# H_Bridge_Motor_Driver_Circuit.net
KiCad netlist of a schematic drawn in EAGLE
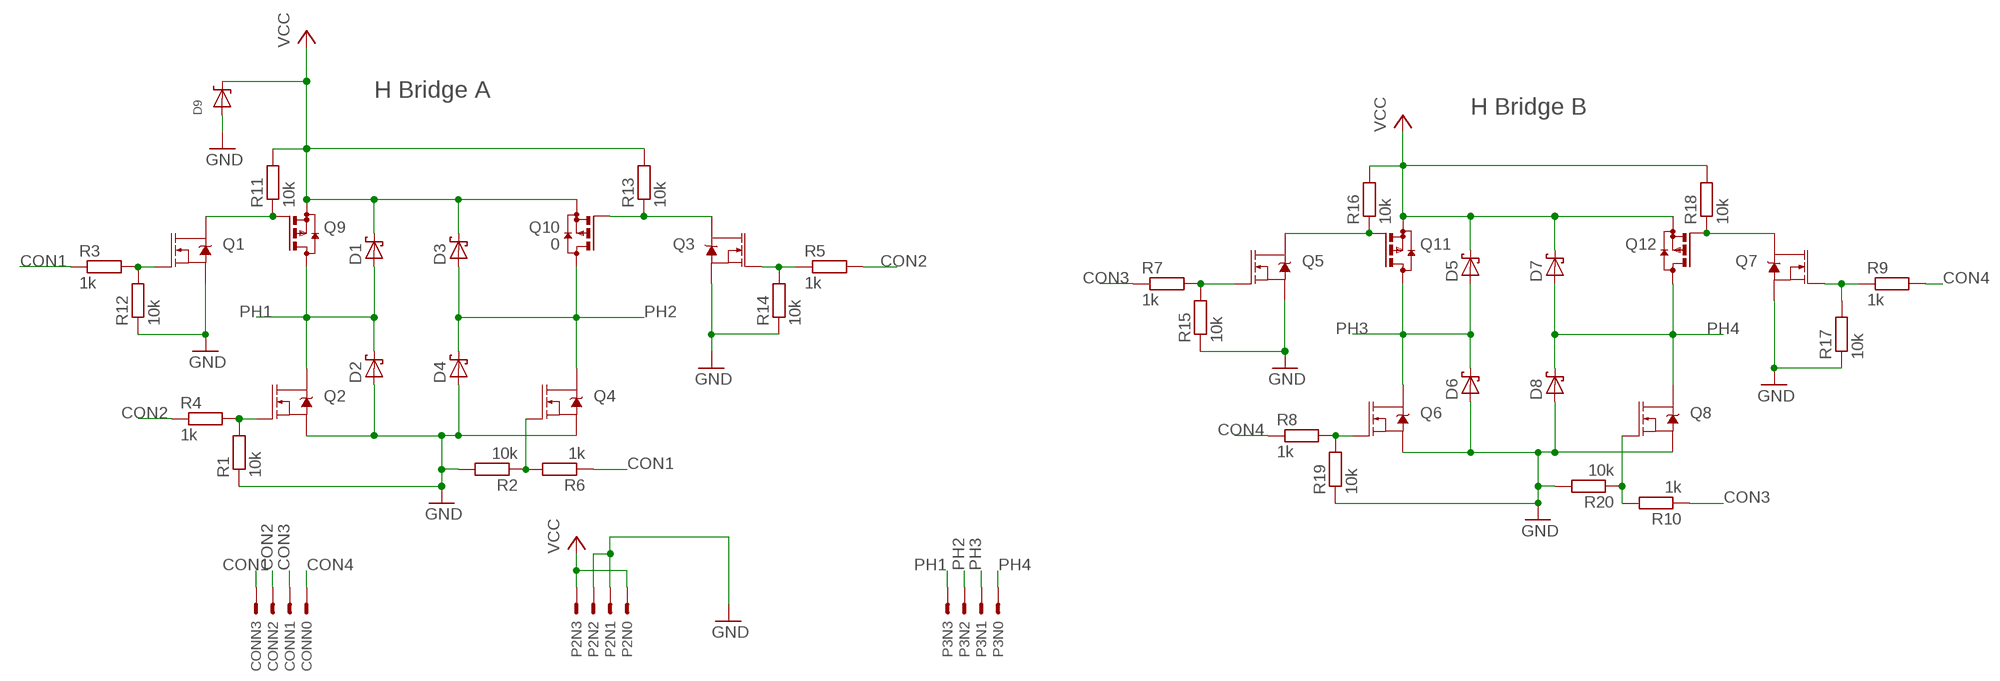
[diagram p0: schematic, sheet 1]

(export (version "E")
  (design (tool "Eeschema 10.0.6"))
  (components
    (comp (ref "CON")
      (value "4PINHEADER")
      (footprint "eagle-import:4PINHEADER")
      (libsource (lib "eagle-import") (part "4PINHEADER"))
    )
    (comp (ref "D1")
      (value "BAS40")
      (footprint "eagle-import:SOT23")
      (libsource (lib "eagle-import") (part "BAS40"))
    )
    (comp (ref "D2")
      (value "BAS40")
      (footprint "eagle-import:SOT23")
      (libsource (lib "eagle-import") (part "BAS40"))
    )
    (comp (ref "D3")
      (value "BAS40")
      (footprint "eagle-import:SOT23")
      (libsource (lib "eagle-import") (part "BAS40"))
    )
    (comp (ref "D4")
      (value "BAS40")
      (footprint "eagle-import:SOT23")
      (libsource (lib "eagle-import") (part "BAS40"))
    )
    (comp (ref "D5")
      (value "BAS40")
      (footprint "eagle-import:SOT23")
      (libsource (lib "eagle-import") (part "BAS40"))
    )
    (comp (ref "D6")
      (value "BAS40")
      (footprint "eagle-import:SOT23")
      (libsource (lib "eagle-import") (part "BAS40"))
    )
    (comp (ref "D7")
      (value "BAS40")
      (footprint "eagle-import:SOT23")
      (libsource (lib "eagle-import") (part "BAS40"))
    )
    (comp (ref "D8")
      (value "BAS40")
      (footprint "eagle-import:SOT23")
      (libsource (lib "eagle-import") (part "BAS40"))
    )
    (comp (ref "D9")
      (value "DDZ5V6ASF")
      (footprint "eagle-import:DDZ5V6ASF")
      (libsource (lib "eagle-import") (part "DDZ5V6ASF"))
    )
    (comp (ref "P2")
      (value "4PINHEADER")
      (footprint "eagle-import:4PINHEADER")
      (libsource (lib "eagle-import") (part "4PINHEADER"))
    )
    (comp (ref "P3")
      (value "4PINHEADER")
      (footprint "eagle-import:4PINHEADER")
      (libsource (lib "eagle-import") (part "4PINHEADER"))
    )
    (comp (ref "Q1")
      (value "MOSFET-NCH-BSS138")
      (footprint "eagle-import:SOT23-3")
      (libsource (lib "eagle-import") (part "MOSFET-NCH-BSS138"))
    )
    (comp (ref "Q2")
      (value "MOSFET-NCH-BSS138")
      (footprint "eagle-import:SOT23-3")
      (libsource (lib "eagle-import") (part "MOSFET-NCH-BSS138"))
    )
    (comp (ref "Q3")
      (value "MOSFET-NCH-BSS138")
      (footprint "eagle-import:SOT23-3")
      (libsource (lib "eagle-import") (part "MOSFET-NCH-BSS138"))
    )
    (comp (ref "Q4")
      (value "MOSFET-NCH-BSS138")
      (footprint "eagle-import:SOT23-3")
      (libsource (lib "eagle-import") (part "MOSFET-NCH-BSS138"))
    )
    (comp (ref "Q5")
      (value "MOSFET-NCH-BSS138")
      (footprint "eagle-import:SOT23-3")
      (libsource (lib "eagle-import") (part "MOSFET-NCH-BSS138"))
    )
    (comp (ref "Q6")
      (value "MOSFET-NCH-BSS138")
      (footprint "eagle-import:SOT23-3")
      (libsource (lib "eagle-import") (part "MOSFET-NCH-BSS138"))
    )
    (comp (ref "Q7")
      (value "MOSFET-NCH-BSS138")
      (footprint "eagle-import:SOT23-3")
      (libsource (lib "eagle-import") (part "MOSFET-NCH-BSS138"))
    )
    (comp (ref "Q8")
      (value "MOSFET-NCH-BSS138")
      (footprint "eagle-import:SOT23-3")
      (libsource (lib "eagle-import") (part "MOSFET-NCH-BSS138"))
    )
    (comp (ref "Q9")
      (value "BSS84")
      (footprint "eagle-import:SOT23")
      (libsource (lib "eagle-import") (part "BSS84"))
    )
    (comp (ref "Q10")
      (value "0")
      (footprint "eagle-import:SOT23")
      (libsource (lib "eagle-import") (part "BSS84"))
    )
    (comp (ref "Q11")
      (value "BSS84")
      (footprint "eagle-import:SOT23")
      (libsource (lib "eagle-import") (part "BSS84"))
    )
    (comp (ref "Q12")
      (value "BSS84")
      (footprint "eagle-import:SOT23")
      (libsource (lib "eagle-import") (part "BSS84"))
    )
    (comp (ref "R1")
      (value "10k")
      (footprint "eagle-import:R1206")
      (libsource (lib "eagle-import") (part "R-EU_R1206"))
    )
    (comp (ref "R2")
      (value "10k")
      (footprint "eagle-import:R1206")
      (libsource (lib "eagle-import") (part "R-EU_R1206"))
    )
    (comp (ref "R3")
      (value "1k")
      (footprint "eagle-import:R1206")
      (libsource (lib "eagle-import") (part "R-EU_R1206"))
    )
    (comp (ref "R4")
      (value "1k")
      (footprint "eagle-import:R1206")
      (libsource (lib "eagle-import") (part "R-EU_R1206"))
    )
    (comp (ref "R5")
      (value "1k")
      (footprint "eagle-import:R1206")
      (libsource (lib "eagle-import") (part "R-EU_R1206"))
    )
    (comp (ref "R6")
      (value "1k")
      (footprint "eagle-import:R1206")
      (libsource (lib "eagle-import") (part "R-EU_R1206"))
    )
    (comp (ref "R7")
      (value "1k")
      (footprint "eagle-import:R1206")
      (libsource (lib "eagle-import") (part "R-EU_R1206"))
    )
    (comp (ref "R8")
      (value "1k")
      (footprint "eagle-import:R1206")
      (libsource (lib "eagle-import") (part "R-EU_R1206"))
    )
    (comp (ref "R9")
      (value "1k")
      (footprint "eagle-import:R1206")
      (libsource (lib "eagle-import") (part "R-EU_R1206"))
    )
    (comp (ref "R10")
      (value "1k")
      (footprint "eagle-import:R1206")
      (libsource (lib "eagle-import") (part "R-EU_R1206"))
    )
    (comp (ref "R11")
      (value "10k")
      (footprint "eagle-import:R1206")
      (libsource (lib "eagle-import") (part "R-EU_R1206"))
    )
    (comp (ref "R12")
      (value "10k")
      (footprint "eagle-import:R1206")
      (libsource (lib "eagle-import") (part "R-EU_R1206"))
    )
    (comp (ref "R13")
      (value "10k")
      (footprint "eagle-import:R1206")
      (libsource (lib "eagle-import") (part "R-EU_R1206"))
    )
    (comp (ref "R14")
      (value "10k")
      (footprint "eagle-import:R1206")
      (libsource (lib "eagle-import") (part "R-EU_R1206"))
    )
    (comp (ref "R15")
      (value "10k")
      (footprint "eagle-import:R1206")
      (libsource (lib "eagle-import") (part "R-EU_R1206"))
    )
    (comp (ref "R16")
      (value "10k")
      (footprint "eagle-import:R1206")
      (libsource (lib "eagle-import") (part "R-EU_R1206"))
    )
    (comp (ref "R17")
      (value "10k")
      (footprint "eagle-import:R1206")
      (libsource (lib "eagle-import") (part "R-EU_R1206"))
    )
    (comp (ref "R18")
      (value "10k")
      (footprint "eagle-import:R1206")
      (libsource (lib "eagle-import") (part "R-EU_R1206"))
    )
    (comp (ref "R19")
      (value "10k")
      (footprint "eagle-import:R1206")
      (libsource (lib "eagle-import") (part "R-EU_R1206"))
    )
    (comp (ref "R20")
      (value "10k")
      (footprint "eagle-import:R1206")
      (libsource (lib "eagle-import") (part "R-EU_R1206"))
    )
  )
  (nets
    (net (code "1") (name "/CON1") (class "Default")
      (node (ref "CON") (pin "N3") (pinfunction "S_N3") (pintype "passive"))
      (node (ref "R3") (pin "1") (pinfunction "1_1") (pintype "passive"))
      (node (ref "R6") (pin "1") (pinfunction "1_1") (pintype "passive"))
    )
    (net (code "2") (name "/CON2") (class "Default")
      (node (ref "CON") (pin "N2") (pinfunction "S_N2") (pintype "passive"))
      (node (ref "R4") (pin "1") (pinfunction "1_1") (pintype "passive"))
      (node (ref "R5") (pin "2") (pinfunction "2_2") (pintype "passive"))
    )
    (net (code "3") (name "/CON3") (class "Default")
      (node (ref "CON") (pin "N1") (pinfunction "S_N1") (pintype "passive"))
      (node (ref "R10") (pin "1") (pinfunction "1_1") (pintype "passive"))
      (node (ref "R7") (pin "1") (pinfunction "1_1") (pintype "passive"))
    )
    (net (code "4") (name "/CON4") (class "Default")
      (node (ref "CON") (pin "N0") (pinfunction "S_N0") (pintype "passive"))
      (node (ref "R8") (pin "1") (pinfunction "1_1") (pintype "passive"))
      (node (ref "R9") (pin "2") (pinfunction "2_2") (pintype "passive"))
    )
    (net (code "5") (name "/PH1") (class "Default")
      (node (ref "D1") (pin "1") (pinfunction "A_1") (pintype "passive"))
      (node (ref "D2") (pin "3") (pinfunction "C_3") (pintype "passive"))
      (node (ref "P3") (pin "N3") (pinfunction "S_N3") (pintype "passive"))
      (node (ref "Q2") (pin "3") (pinfunction "D_3") (pintype "bidirectional"))
      (node (ref "Q9") (pin "3") (pinfunction "D_3") (pintype "passive"))
    )
    (net (code "6") (name "/PH2") (class "Default")
      (node (ref "D3") (pin "1") (pinfunction "A_1") (pintype "passive"))
      (node (ref "D4") (pin "3") (pinfunction "C_3") (pintype "passive"))
      (node (ref "P3") (pin "N2") (pinfunction "S_N2") (pintype "passive"))
      (node (ref "Q10") (pin "3") (pinfunction "D_3") (pintype "passive"))
      (node (ref "Q4") (pin "3") (pinfunction "D_3") (pintype "bidirectional"))
    )
    (net (code "7") (name "/PH3") (class "Default")
      (node (ref "D5") (pin "1") (pinfunction "A_1") (pintype "passive"))
      (node (ref "D6") (pin "3") (pinfunction "C_3") (pintype "passive"))
      (node (ref "P3") (pin "N1") (pinfunction "S_N1") (pintype "passive"))
      (node (ref "Q11") (pin "3") (pinfunction "D_3") (pintype "passive"))
      (node (ref "Q6") (pin "3") (pinfunction "D_3") (pintype "bidirectional"))
    )
    (net (code "8") (name "/PH4") (class "Default")
      (node (ref "D7") (pin "1") (pinfunction "A_1") (pintype "passive"))
      (node (ref "D8") (pin "3") (pinfunction "C_3") (pintype "passive"))
      (node (ref "P3") (pin "N0") (pinfunction "S_N0") (pintype "passive"))
      (node (ref "Q12") (pin "3") (pinfunction "D_3") (pintype "passive"))
      (node (ref "Q8") (pin "3") (pinfunction "D_3") (pintype "bidirectional"))
    )
    (net (code "9") (name "GND") (class "Default")
      (node (ref "D2") (pin "1") (pinfunction "A_1") (pintype "passive"))
      (node (ref "D4") (pin "1") (pinfunction "A_1") (pintype "passive"))
      (node (ref "D6") (pin "1") (pinfunction "A_1") (pintype "passive"))
      (node (ref "D8") (pin "1") (pinfunction "A_1") (pintype "passive"))
      (node (ref "D9") (pin "P$1") (pinfunction "A_P$1") (pintype "passive"))
      (node (ref "P2") (pin "N1") (pinfunction "S_N1") (pintype "passive"))
      (node (ref "P2") (pin "N2") (pinfunction "S_N2") (pintype "passive"))
      (node (ref "Q1") (pin "2") (pinfunction "S_2") (pintype "bidirectional"))
      (node (ref "Q2") (pin "2") (pinfunction "S_2") (pintype "bidirectional"))
      (node (ref "Q3") (pin "2") (pinfunction "S_2") (pintype "bidirectional"))
      (node (ref "Q4") (pin "2") (pinfunction "S_2") (pintype "bidirectional"))
      (node (ref "Q5") (pin "2") (pinfunction "S_2") (pintype "bidirectional"))
      (node (ref "Q6") (pin "2") (pinfunction "S_2") (pintype "bidirectional"))
      (node (ref "Q7") (pin "2") (pinfunction "S_2") (pintype "bidirectional"))
      (node (ref "Q8") (pin "2") (pinfunction "S_2") (pintype "bidirectional"))
      (node (ref "R1") (pin "1") (pinfunction "1_1") (pintype "passive"))
      (node (ref "R12") (pin "1") (pinfunction "1_1") (pintype "passive"))
      (node (ref "R14") (pin "1") (pinfunction "1_1") (pintype "passive"))
      (node (ref "R15") (pin "1") (pinfunction "1_1") (pintype "passive"))
      (node (ref "R17") (pin "1") (pinfunction "1_1") (pintype "passive"))
      (node (ref "R19") (pin "1") (pinfunction "1_1") (pintype "passive"))
      (node (ref "R2") (pin "2") (pinfunction "2_2") (pintype "passive"))
      (node (ref "R20") (pin "2") (pinfunction "2_2") (pintype "passive"))
    )
    (net (code "10") (name "Net-(Q1-D)") (class "Default")
      (node (ref "Q1") (pin "3") (pinfunction "D_3") (pintype "bidirectional"))
      (node (ref "Q9") (pin "1") (pinfunction "G_1") (pintype "passive"))
      (node (ref "R11") (pin "1") (pinfunction "1_1") (pintype "passive"))
    )
    (net (code "11") (name "Net-(Q1-G)") (class "Default")
      (node (ref "Q1") (pin "1") (pinfunction "G_1") (pintype "bidirectional"))
      (node (ref "R12") (pin "2") (pinfunction "2_2") (pintype "passive"))
      (node (ref "R3") (pin "2") (pinfunction "2_2") (pintype "passive"))
    )
    (net (code "12") (name "Net-(Q2-G)") (class "Default")
      (node (ref "Q2") (pin "1") (pinfunction "G_1") (pintype "bidirectional"))
      (node (ref "R1") (pin "2") (pinfunction "2_2") (pintype "passive"))
      (node (ref "R4") (pin "2") (pinfunction "2_2") (pintype "passive"))
    )
    (net (code "13") (name "Net-(Q3-G)") (class "Default")
      (node (ref "Q3") (pin "1") (pinfunction "G_1") (pintype "bidirectional"))
      (node (ref "R14") (pin "2") (pinfunction "2_2") (pintype "passive"))
      (node (ref "R5") (pin "1") (pinfunction "1_1") (pintype "passive"))
    )
    (net (code "14") (name "Net-(Q4-G)") (class "Default")
      (node (ref "Q4") (pin "1") (pinfunction "G_1") (pintype "bidirectional"))
      (node (ref "R2") (pin "1") (pinfunction "1_1") (pintype "passive"))
      (node (ref "R6") (pin "2") (pinfunction "2_2") (pintype "passive"))
    )
    (net (code "15") (name "Net-(Q5-G)") (class "Default")
      (node (ref "Q5") (pin "1") (pinfunction "G_1") (pintype "bidirectional"))
      (node (ref "R15") (pin "2") (pinfunction "2_2") (pintype "passive"))
      (node (ref "R7") (pin "2") (pinfunction "2_2") (pintype "passive"))
    )
    (net (code "16") (name "Net-(Q6-G)") (class "Default")
      (node (ref "Q6") (pin "1") (pinfunction "G_1") (pintype "bidirectional"))
      (node (ref "R19") (pin "2") (pinfunction "2_2") (pintype "passive"))
      (node (ref "R8") (pin "2") (pinfunction "2_2") (pintype "passive"))
    )
    (net (code "17") (name "Net-(Q7-G)") (class "Default")
      (node (ref "Q7") (pin "1") (pinfunction "G_1") (pintype "bidirectional"))
      (node (ref "R17") (pin "2") (pinfunction "2_2") (pintype "passive"))
      (node (ref "R9") (pin "1") (pinfunction "1_1") (pintype "passive"))
    )
    (net (code "18") (name "Net-(Q8-G)") (class "Default")
      (node (ref "Q8") (pin "1") (pinfunction "G_1") (pintype "bidirectional"))
      (node (ref "R10") (pin "2") (pinfunction "2_2") (pintype "passive"))
      (node (ref "R20") (pin "1") (pinfunction "1_1") (pintype "passive"))
    )
    (net (code "19") (name "Net-(Q10-G)") (class "Default")
      (node (ref "Q10") (pin "1") (pinfunction "G_1") (pintype "passive"))
      (node (ref "Q3") (pin "3") (pinfunction "D_3") (pintype "bidirectional"))
      (node (ref "R13") (pin "1") (pinfunction "1_1") (pintype "passive"))
    )
    (net (code "20") (name "Net-(Q11-G)") (class "Default")
      (node (ref "Q11") (pin "1") (pinfunction "G_1") (pintype "passive"))
      (node (ref "Q5") (pin "3") (pinfunction "D_3") (pintype "bidirectional"))
      (node (ref "R16") (pin "1") (pinfunction "1_1") (pintype "passive"))
    )
    (net (code "21") (name "Net-(Q12-G)") (class "Default")
      (node (ref "Q12") (pin "1") (pinfunction "G_1") (pintype "passive"))
      (node (ref "Q7") (pin "3") (pinfunction "D_3") (pintype "bidirectional"))
      (node (ref "R18") (pin "1") (pinfunction "1_1") (pintype "passive"))
    )
    (net (code "22") (name "VCC") (class "Default")
      (node (ref "D1") (pin "3") (pinfunction "C_3") (pintype "passive"))
      (node (ref "D3") (pin "3") (pinfunction "C_3") (pintype "passive"))
      (node (ref "D5") (pin "3") (pinfunction "C_3") (pintype "passive"))
      (node (ref "D7") (pin "3") (pinfunction "C_3") (pintype "passive"))
      (node (ref "D9") (pin "P$2") (pinfunction "C_P$2") (pintype "passive"))
      (node (ref "P2") (pin "N0") (pinfunction "S_N0") (pintype "passive"))
      (node (ref "P2") (pin "N3") (pinfunction "S_N3") (pintype "passive"))
      (node (ref "Q10") (pin "2") (pinfunction "S_2") (pintype "passive"))
      (node (ref "Q11") (pin "2") (pinfunction "S_2") (pintype "passive"))
      (node (ref "Q12") (pin "2") (pinfunction "S_2") (pintype "passive"))
      (node (ref "Q9") (pin "2") (pinfunction "S_2") (pintype "passive"))
      (node (ref "R11") (pin "2") (pinfunction "2_2") (pintype "passive"))
      (node (ref "R13") (pin "2") (pinfunction "2_2") (pintype "passive"))
      (node (ref "R16") (pin "2") (pinfunction "2_2") (pintype "passive"))
      (node (ref "R18") (pin "2") (pinfunction "2_2") (pintype "passive"))
    )
  )
)
